# Sheet5.net
KiCad netlist of a schematic drawn in Altium Designer
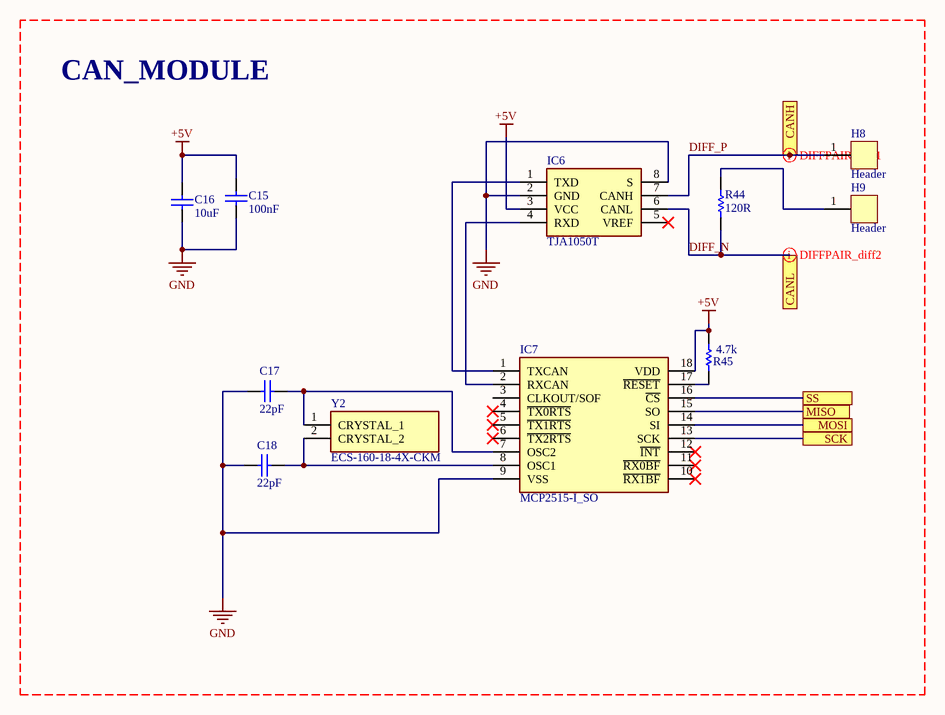
[diagram p0: Sheet5.SchDoc]

(export (version "E")
  (design (tool "Eeschema 10.0.6"))
  (components
    (comp (ref "C15")
      (value "100nF")
      (footprint "KEMT-1206-2_N")
      (description "CAP, Ceramic, 0.1 uF, +/- 10%, 50 V, -55 to 125 degC, 1206 (3216 Metric), RoHS, Tape and Reel")
      (fields (field (name "MANUFACTURER") "Kemet"))
      (libsource (lib "Schlib1") (part "CMP-1037-04202-2"))
    )
    (comp (ref "C16")
      (value "10uF")
      (footprint "KEMT-1206-2_N")
      (description "CAP, Ceramic, 0.1 uF, +/- 10%, 50 V, -55 to 125 degC, 1206 (3216 Metric), RoHS, Tape and Reel")
      (fields (field (name "MANUFACTURER") "Kemet"))
      (libsource (lib "Schlib1") (part "CMP-1037-04202-2"))
    )
    (comp (ref "C17")
      (value "22pF")
      (footprint "KEMT-1206-2_N")
      (description "CAP, Ceramic, 0.1 uF, +/- 10%, 50 V, -55 to 125 degC, 1206 (3216 Metric), RoHS, Tape and Reel")
      (fields (field (name "MANUFACTURER") "Kemet"))
      (libsource (lib "Schlib1") (part "CMP-1037-04202-2"))
    )
    (comp (ref "C18")
      (value "22pF")
      (footprint "KEMT-1206-2_N")
      (description "CAP, Ceramic, 0.1 uF, +/- 10%, 50 V, -55 to 125 degC, 1206 (3216 Metric), RoHS, Tape and Reel")
      (fields (field (name "MANUFACTURER") "Kemet"))
      (libsource (lib "Schlib1") (part "CMP-1037-04202-2"))
    )
    (comp (ref "H8") (value "Header") (footprint "Header") (libsource (lib "Schlib1") (part "Header")))
    (comp (ref "H9") (value "Header") (footprint "Header") (libsource (lib "Schlib1") (part "Header")))
    (comp (ref "IC6")
      (value "TJA1050T")
      (footprint "SamacSys:SOIC127P600X175-8N")
      (description "Integrated Circuit")
      (libsource (lib "SamacSys") (part "TJA1050T"))
    )
    (comp (ref "IC7")
      (value "MCP2515-I_SO")
      (footprint "SamacSys:SOIC127P1030X265-18N")
      (description "Integrated Circuit")
      (fields
        (field (name "MANUFACTURER_PART_NUMBER") "MCP2515-I/SO")
        (field (name "MOUSER PART NUMBER") "579-MCP2515-I/SO")
      )
      (libsource (lib "SamacSys") (part "MCP2515-I_SO"))
    )
    (comp (ref "R44")
      (value "120R")
      (footprint "R1206")
      (fields (field (name "PART NUMBER") "CRCW120647K0FKEA") (field (name "MANUFACTURER") "Vishay Dale"))
      (libsource (lib "SamacSys") (part "RES"))
    )
    (comp (ref "R45")
      (value "4.7k")
      (footprint "R1206")
      (fields (field (name "PART NUMBER") "CRCW120647K0FKEA") (field (name "MANUFACTURER") "Vishay Dale"))
      (libsource (lib "SamacSys") (part "RES"))
    )
    (comp (ref "Y2")
      (value "ECS-160-18-4X-CKM")
      (footprint "SamacSys:ECS160184XCKM")
      (description "Crystal or Oscillator")
      (fields (field (name "MOUSER PART NUMBER") "520-ECS160-18-4X-CKM"))
      (libsource (lib "SamacSys") (part "ECS-160-18-4X-CKM"))
    )
  )
  (nets
    (net (code "1") (name "+5V") (class "Default")
      (node (ref "C15") (pin "1") (pinfunction "1_1") (pintype "passive"))
      (node (ref "C16") (pin "1") (pinfunction "1_1") (pintype "passive"))
      (node (ref "IC6") (pin "3") (pinfunction "VCC_3") (pintype "passive"))
      (node (ref "IC7") (pin "18") (pinfunction "VDD_18") (pintype "passive"))
      (node (ref "R45") (pin "1") (pinfunction "1_1") (pintype "passive"))
    )
    (net (code "2") (name "/DIFF_N") (class "Default")
      (node (ref "IC6") (pin "6") (pinfunction "CANL_6") (pintype "passive"))
      (node (ref "R44") (pin "1") (pinfunction "1_1") (pintype "passive"))
    )
    (net (code "3") (name "/DIFF_P") (class "Default")
      (node (ref "H8") (pin "1") (pinfunction "1_1") (pintype "passive"))
      (node (ref "IC6") (pin "7") (pinfunction "CANH_7") (pintype "passive"))
    )
    (net (code "4") (name "/MISO") (class "Default")
      (node (ref "IC7") (pin "15") (pinfunction "SO_15") (pintype "passive"))
    )
    (net (code "5") (name "/MOSI") (class "Default")
      (node (ref "IC7") (pin "14") (pinfunction "SI_14") (pintype "passive"))
    )
    (net (code "6") (name "/SCK") (class "Default")
      (node (ref "IC7") (pin "13") (pinfunction "SCK_13") (pintype "passive"))
    )
    (net (code "7") (name "/SS") (class "Default")
      (node (ref "IC7") (pin "16") (pinfunction "~{CS}_16") (pintype "passive"))
    )
    (net (code "8") (name "GND") (class "Default")
      (node (ref "C15") (pin "2") (pinfunction "2_2") (pintype "passive"))
      (node (ref "C16") (pin "2") (pinfunction "2_2") (pintype "passive"))
      (node (ref "C17") (pin "2") (pinfunction "2_2") (pintype "passive"))
      (node (ref "C18") (pin "2") (pinfunction "2_2") (pintype "passive"))
      (node (ref "IC6") (pin "2") (pinfunction "GND_2") (pintype "passive"))
      (node (ref "IC6") (pin "8") (pinfunction "S_8") (pintype "passive"))
      (node (ref "IC7") (pin "9") (pinfunction "VSS_9") (pintype "passive"))
    )
    (net (code "9") (name "Net-(H9-Pad1)") (class "Default")
      (node (ref "H9") (pin "1") (pinfunction "1_1") (pintype "passive"))
      (node (ref "R44") (pin "2") (pinfunction "2_2") (pintype "passive"))
    )
    (net (code "10") (name "Net-(IC6-RXD)") (class "Default")
      (node (ref "IC6") (pin "4") (pinfunction "RXD_4") (pintype "passive"))
      (node (ref "IC7") (pin "2") (pinfunction "RXCAN_2") (pintype "passive"))
    )
    (net (code "11") (name "Net-(IC6-TXD)") (class "Default")
      (node (ref "IC6") (pin "1") (pinfunction "TXD_1") (pintype "passive"))
      (node (ref "IC7") (pin "1") (pinfunction "TXCAN_1") (pintype "passive"))
    )
    (net (code "12") (name "Net-(IC7-OSC1)") (class "Default")
      (node (ref "C18") (pin "1") (pinfunction "1_1") (pintype "passive"))
      (node (ref "IC7") (pin "8") (pinfunction "OSC1_8") (pintype "passive"))
      (node (ref "Y2") (pin "2") (pinfunction "CRYSTAL_2_2") (pintype "passive"))
    )
    (net (code "13") (name "Net-(IC7-OSC2)") (class "Default")
      (node (ref "C17") (pin "1") (pinfunction "1_1") (pintype "passive"))
      (node (ref "IC7") (pin "7") (pinfunction "OSC2_7") (pintype "passive"))
      (node (ref "Y2") (pin "1") (pinfunction "CRYSTAL_1_1") (pintype "passive"))
    )
    (net (code "14") (name "Net-(IC7-~{RESET})") (class "Default")
      (node (ref "IC7") (pin "17") (pinfunction "~{RESET}_17") (pintype "passive"))
      (node (ref "R45") (pin "2") (pinfunction "2_2") (pintype "passive"))
    )
    (net (code "15") (name "unconnected-(IC6-VREF-Pad5)") (class "Default")
      (node (ref "IC6") (pin "5") (pinfunction "VREF_5") (pintype "passive+no_connect"))
    )
    (net (code "16") (name "unconnected-(IC7-CLKOUT{slash}SOF-Pad3)") (class "Default")
      (node (ref "IC7") (pin "3") (pinfunction "CLKOUT/SOF_3") (pintype "passive"))
    )
    (net (code "17") (name "unconnected-(IC7-~{INT}-Pad12)") (class "Default")
      (node (ref "IC7") (pin "12") (pinfunction "~{INT}_12") (pintype "passive+no_connect"))
    )
    (net (code "18") (name "unconnected-(IC7-~{RX0BF}-Pad11)") (class "Default")
      (node (ref "IC7") (pin "11") (pinfunction "~{RX0BF}_11") (pintype "passive+no_connect"))
    )
    (net (code "19") (name "unconnected-(IC7-~{RX1BF}-Pad10)") (class "Default")
      (node (ref "IC7") (pin "10") (pinfunction "~{RX1BF}_10") (pintype "passive+no_connect"))
    )
    (net (code "20") (name "unconnected-(IC7-~{TX0RTS}-Pad4)") (class "Default")
      (node (ref "IC7") (pin "4") (pinfunction "~{TX0RTS}_4") (pintype "passive+no_connect"))
    )
    (net (code "21") (name "unconnected-(IC7-~{TX1RTS}-Pad5)") (class "Default")
      (node (ref "IC7") (pin "5") (pinfunction "~{TX1RTS}_5") (pintype "passive+no_connect"))
    )
    (net (code "22") (name "unconnected-(IC7-~{TX2RTS}-Pad6)") (class "Default")
      (node (ref "IC7") (pin "6") (pinfunction "~{TX2RTS}_6") (pintype "passive+no_connect"))
    )
  )
)
